# main_unit_shield.net
KiCad netlist of a schematic drawn in EAGLE
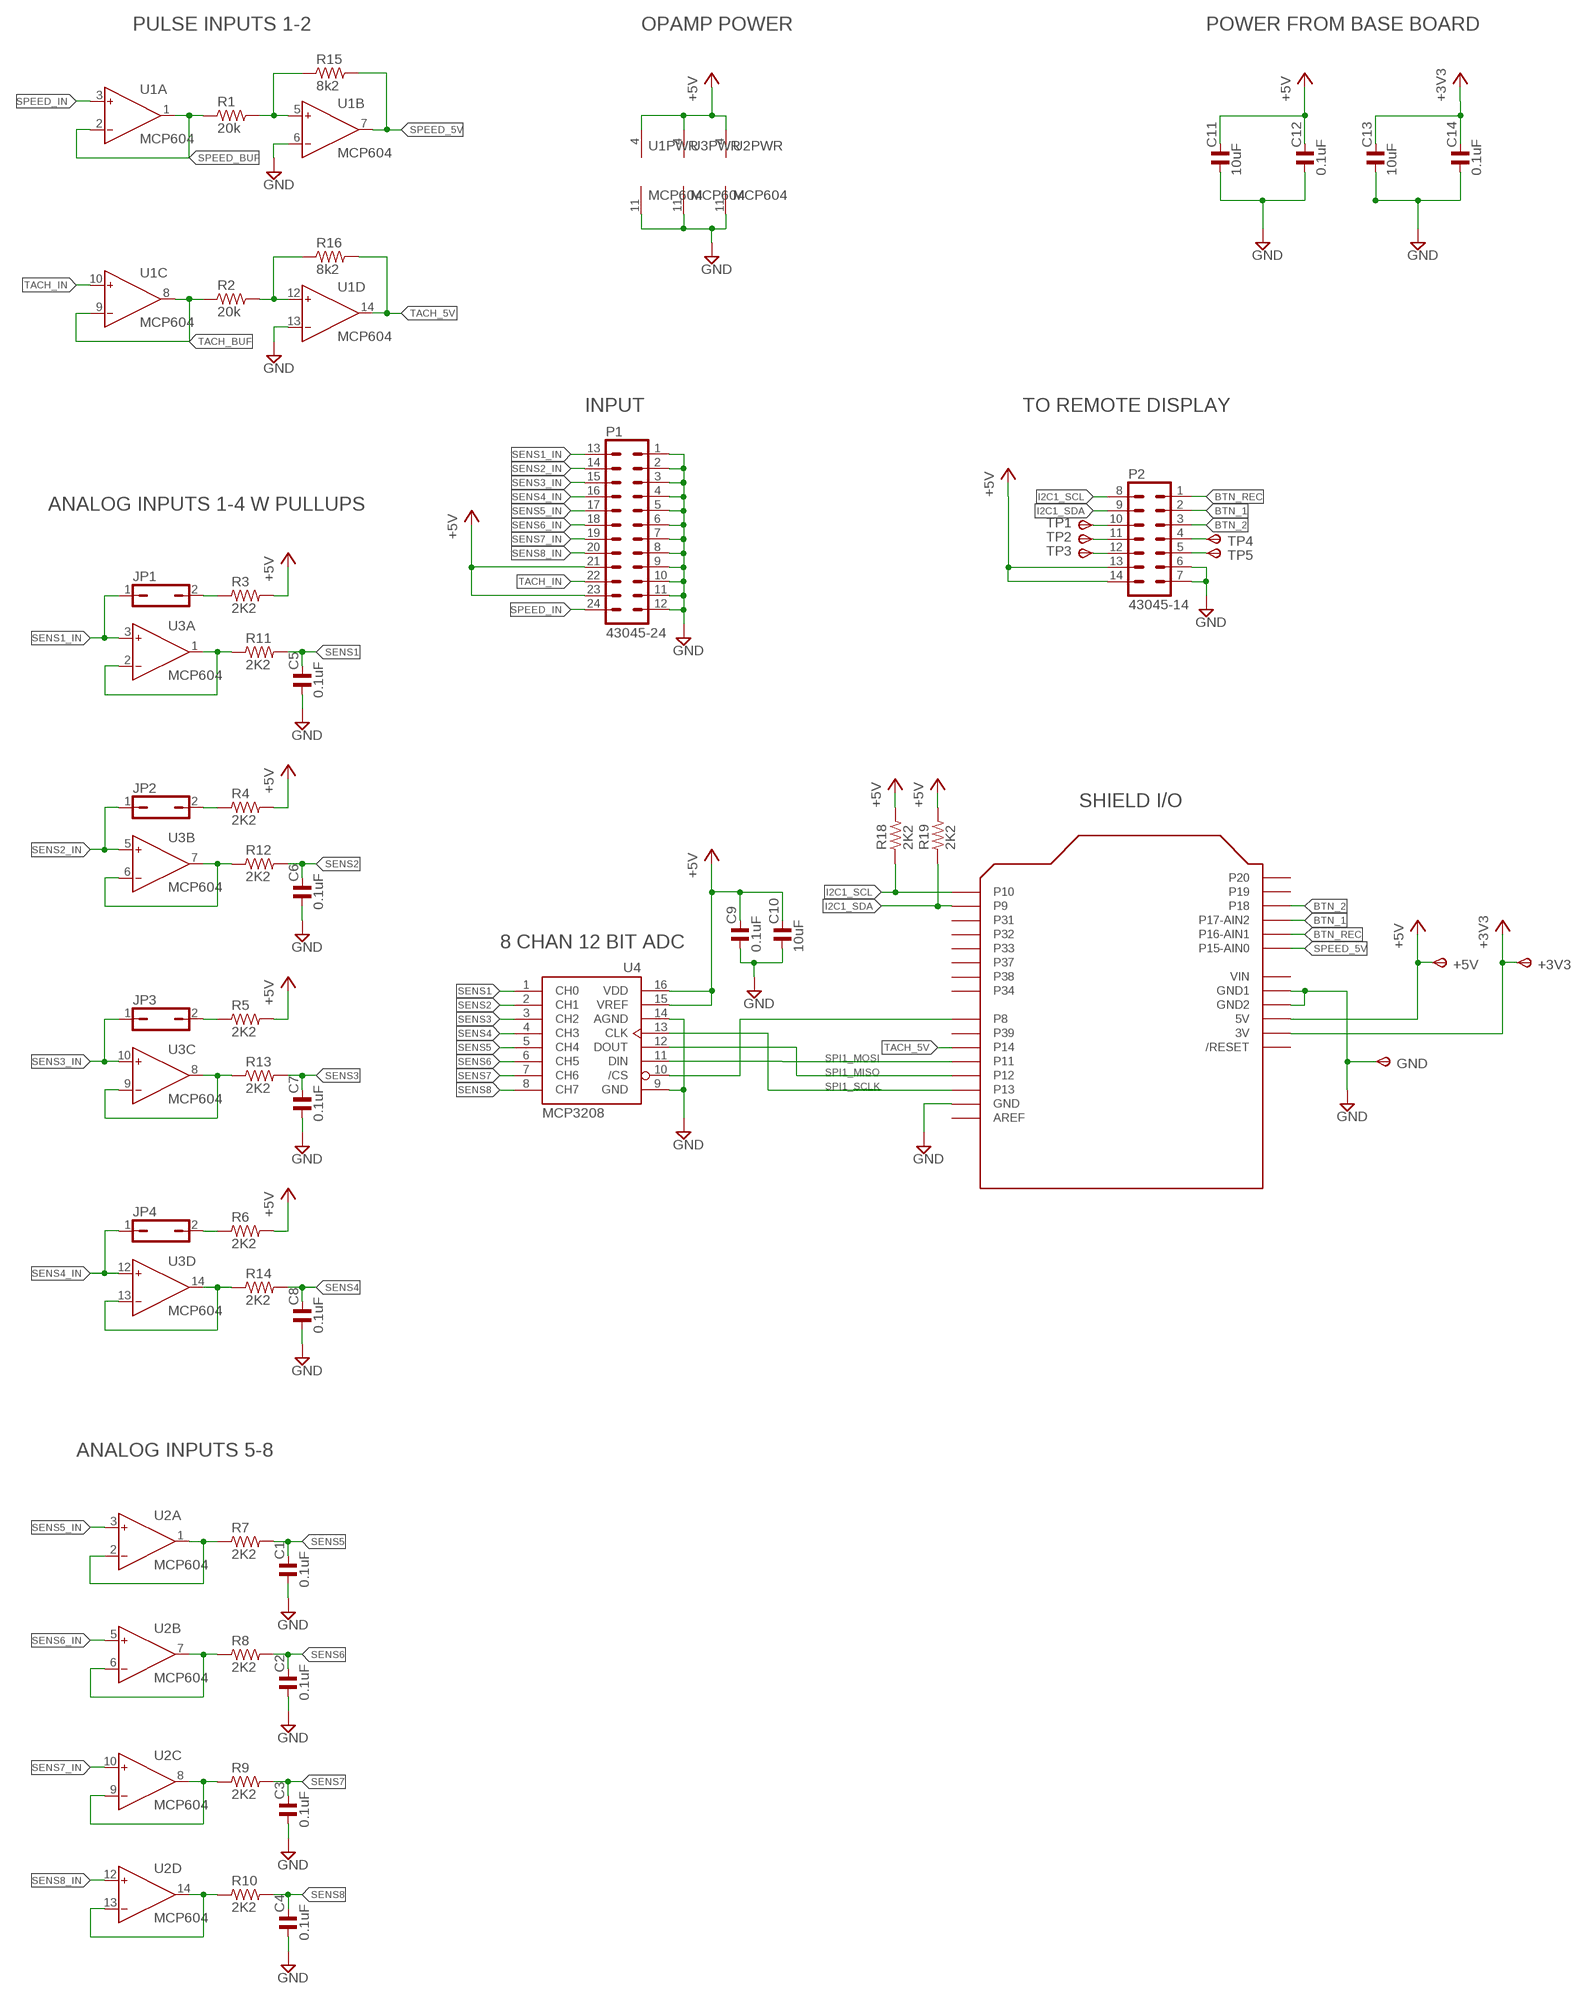
[diagram p0: schematic, sheet 1]

(export (version "E")
  (design (tool "Eeschema 10.0.6"))
  (components
    (comp (ref "+3V3")
      (value "TPSPAD1-13")
      (footprint "eagle-import:P1-13")
      (libsource (lib "eagle-import") (part "TPSPAD1-13"))
    )
    (comp (ref "+5V")
      (value "TPSPAD1-13")
      (footprint "eagle-import:P1-13")
      (libsource (lib "eagle-import") (part "TPSPAD1-13"))
    )
    (comp (ref "C1")
      (value "0.1uF")
      (footprint "eagle-import:C0805")
      (fields (field (name "MPN") "C2012X7R1H104K085AA"))
      (libsource (lib "eagle-import") (part "C_0805"))
    )
    (comp (ref "C2")
      (value "0.1uF")
      (footprint "eagle-import:C0805")
      (fields (field (name "MPN") "C2012X7R1H104K085AA"))
      (libsource (lib "eagle-import") (part "C_0805"))
    )
    (comp (ref "C3")
      (value "0.1uF")
      (footprint "eagle-import:C0805")
      (fields (field (name "MPN") "C2012X7R1H104K085AA"))
      (libsource (lib "eagle-import") (part "C_0805"))
    )
    (comp (ref "C4")
      (value "0.1uF")
      (footprint "eagle-import:C0805")
      (fields (field (name "MPN") "C2012X7R1H104K085AA"))
      (libsource (lib "eagle-import") (part "C_0805"))
    )
    (comp (ref "C5")
      (value "0.1uF")
      (footprint "eagle-import:C0805")
      (fields (field (name "MPN") "C2012X7R1H104K085AA"))
      (libsource (lib "eagle-import") (part "C_0805"))
    )
    (comp (ref "C6")
      (value "0.1uF")
      (footprint "eagle-import:C0805")
      (fields (field (name "MPN") "C2012X7R1H104K085AA"))
      (libsource (lib "eagle-import") (part "C_0805"))
    )
    (comp (ref "C7")
      (value "0.1uF")
      (footprint "eagle-import:C0805")
      (fields (field (name "MPN") "C2012X7R1H104K085AA"))
      (libsource (lib "eagle-import") (part "C_0805"))
    )
    (comp (ref "C8")
      (value "0.1uF")
      (footprint "eagle-import:C0805")
      (fields (field (name "MPN") "C2012X7R1H104K085AA"))
      (libsource (lib "eagle-import") (part "C_0805"))
    )
    (comp (ref "C9")
      (value "0.1uF")
      (footprint "eagle-import:C0805")
      (fields (field (name "MPN") "C2012X7R1H104K085AA"))
      (libsource (lib "eagle-import") (part "C_0805"))
    )
    (comp (ref "C10")
      (value "10uF")
      (footprint "eagle-import:C0805")
      (fields (field (name "MPN") "C2012X5R1E106K125AB"))
      (libsource (lib "eagle-import") (part "C_0805"))
    )
    (comp (ref "C11")
      (value "10uF")
      (footprint "eagle-import:C0805")
      (fields (field (name "MPN") "C2012X5R1E106K125AB"))
      (libsource (lib "eagle-import") (part "C_0805"))
    )
    (comp (ref "C12")
      (value "0.1uF")
      (footprint "eagle-import:C0805")
      (fields (field (name "MPN") "C2012X7R1H104K085AA"))
      (libsource (lib "eagle-import") (part "C_0805"))
    )
    (comp (ref "C13")
      (value "10uF")
      (footprint "eagle-import:C0805")
      (fields (field (name "MPN") "C2012X5R1E106K125AB"))
      (libsource (lib "eagle-import") (part "C_0805"))
    )
    (comp (ref "C14")
      (value "0.1uF")
      (footprint "eagle-import:C0805")
      (fields (field (name "MPN") "C2012X7R1H104K085AA"))
      (libsource (lib "eagle-import") (part "C_0805"))
    )
    (comp (ref "GND")
      (value "TPSPAD1-13")
      (footprint "eagle-import:P1-13")
      (libsource (lib "eagle-import") (part "TPSPAD1-13"))
    )
    (comp (ref "JP1")
      (value "JP1Q")
      (footprint "eagle-import:JP1")
      (fields (field (name "MPN") "969102-0000-DA"))
      (libsource (lib "eagle-import") (part "JP1Q"))
    )
    (comp (ref "JP2")
      (value "JP1Q")
      (footprint "eagle-import:JP1")
      (fields (field (name "MPN") "969102-0000-DA"))
      (libsource (lib "eagle-import") (part "JP1Q"))
    )
    (comp (ref "JP3")
      (value "JP1Q")
      (footprint "eagle-import:JP1")
      (fields (field (name "MPN") "969102-0000-DA"))
      (libsource (lib "eagle-import") (part "JP1Q"))
    )
    (comp (ref "JP4")
      (value "JP1Q")
      (footprint "eagle-import:JP1")
      (fields (field (name "MPN") "969102-0000-DA"))
      (libsource (lib "eagle-import") (part "JP1Q"))
    )
    (comp (ref "P1")
      (value "43045-24")
      (footprint "eagle-import:43045-24")
      (fields (field (name "MF") "MOLEX") (field (name "MPN") "43045-2400"))
      (libsource (lib "eagle-import") (part "43045-24"))
    )
    (comp (ref "P2")
      (value "43045-14")
      (footprint "eagle-import:43045-14")
      (fields (field (name "MPN") "43045-1400"))
      (libsource (lib "eagle-import") (part "43045-14"))
    )
    (comp (ref "R1")
      (value "20k")
      (footprint "eagle-import:R0805")
      (fields (field (name "MF") "VISHAY/DALE") (field (name "MPN") "CRCW080520K0FKEA"))
      (libsource (lib "eagle-import") (part "R_0805"))
    )
    (comp (ref "R2")
      (value "20k")
      (footprint "eagle-import:R0805")
      (fields (field (name "MF") "VISHAY/DALE") (field (name "MPN") "CRCW080520K0FKEA"))
      (libsource (lib "eagle-import") (part "R_0805"))
    )
    (comp (ref "R3")
      (value "2K2")
      (footprint "eagle-import:R0805")
      (fields (field (name "MF") "VISHAY/DALE") (field (name "MPN") "CRCW08052K20FKEA"))
      (libsource (lib "eagle-import") (part "R_0805"))
    )
    (comp (ref "R4")
      (value "2K2")
      (footprint "eagle-import:R0805")
      (fields (field (name "MF") "VISHAY/DALE") (field (name "MPN") "CRCW08052K20FKEA"))
      (libsource (lib "eagle-import") (part "R_0805"))
    )
    (comp (ref "R5")
      (value "2K2")
      (footprint "eagle-import:R0805")
      (fields (field (name "MF") "VISHAY/DALE") (field (name "MPN") "CRCW08052K20FKEA"))
      (libsource (lib "eagle-import") (part "R_0805"))
    )
    (comp (ref "R6")
      (value "2K2")
      (footprint "eagle-import:R0805")
      (fields (field (name "MF") "VISHAY/DALE") (field (name "MPN") "CRCW08052K20FKEA"))
      (libsource (lib "eagle-import") (part "R_0805"))
    )
    (comp (ref "R7")
      (value "2K2")
      (footprint "eagle-import:R0805")
      (fields (field (name "MF") "VISHAY/DALE") (field (name "MPN") "CRCW08052K20FKEA"))
      (libsource (lib "eagle-import") (part "R_0805"))
    )
    (comp (ref "R8")
      (value "2K2")
      (footprint "eagle-import:R0805")
      (fields (field (name "MF") "VISHAY/DALE") (field (name "MPN") "CRCW08052K20FKEA"))
      (libsource (lib "eagle-import") (part "R_0805"))
    )
    (comp (ref "R9")
      (value "2K2")
      (footprint "eagle-import:R0805")
      (fields (field (name "MF") "VISHAY/DALE") (field (name "MPN") "CRCW08052K20FKEA"))
      (libsource (lib "eagle-import") (part "R_0805"))
    )
    (comp (ref "R10")
      (value "2K2")
      (footprint "eagle-import:R0805")
      (fields (field (name "MF") "VISHAY/DALE") (field (name "MPN") "CRCW08052K20FKEA"))
      (libsource (lib "eagle-import") (part "R_0805"))
    )
    (comp (ref "R11")
      (value "2K2")
      (footprint "eagle-import:R0805")
      (fields (field (name "MF") "VISHAY/DALE") (field (name "MPN") "CRCW08052K20FKEA"))
      (libsource (lib "eagle-import") (part "R_0805"))
    )
    (comp (ref "R12")
      (value "2K2")
      (footprint "eagle-import:R0805")
      (fields (field (name "MF") "VISHAY/DALE") (field (name "MPN") "CRCW08052K20FKEA"))
      (libsource (lib "eagle-import") (part "R_0805"))
    )
    (comp (ref "R13")
      (value "2K2")
      (footprint "eagle-import:R0805")
      (fields (field (name "MF") "VISHAY/DALE") (field (name "MPN") "CRCW08052K20FKEA"))
      (libsource (lib "eagle-import") (part "R_0805"))
    )
    (comp (ref "R14")
      (value "2K2")
      (footprint "eagle-import:R0805")
      (fields (field (name "MF") "VISHAY/DALE") (field (name "MPN") "CRCW08052K20FKEA"))
      (libsource (lib "eagle-import") (part "R_0805"))
    )
    (comp (ref "R15")
      (value "8k2")
      (footprint "eagle-import:R0805")
      (fields (field (name "MPN") "CRCW08058K20FKEAHP"))
      (libsource (lib "eagle-import") (part "R_0805"))
    )
    (comp (ref "R16")
      (value "8k2")
      (footprint "eagle-import:R0805")
      (fields (field (name "MPN") "CRCW08058K20FKEAHP"))
      (libsource (lib "eagle-import") (part "R_0805"))
    )
    (comp (ref "R18")
      (value "2K2")
      (footprint "eagle-import:R0805")
      (fields (field (name "MF") "VISHAY/DALE") (field (name "MPN") "CRCW08052K20FKEA"))
      (libsource (lib "eagle-import") (part "R_0805"))
    )
    (comp (ref "R19")
      (value "2K2")
      (footprint "eagle-import:R0805")
      (fields (field (name "MF") "VISHAY/DALE") (field (name "MPN") "CRCW08052K20FKEA"))
      (libsource (lib "eagle-import") (part "R_0805"))
    )
    (comp (ref "TP1")
      (value "TPSPAD1-13")
      (footprint "eagle-import:P1-13")
      (libsource (lib "eagle-import") (part "TPSPAD1-13"))
    )
    (comp (ref "TP2")
      (value "TPSPAD1-13")
      (footprint "eagle-import:P1-13")
      (libsource (lib "eagle-import") (part "TPSPAD1-13"))
    )
    (comp (ref "TP3")
      (value "TPSPAD1-13")
      (footprint "eagle-import:P1-13")
      (libsource (lib "eagle-import") (part "TPSPAD1-13"))
    )
    (comp (ref "TP4")
      (value "TPSPAD1-13")
      (footprint "eagle-import:P1-13")
      (libsource (lib "eagle-import") (part "TPSPAD1-13"))
    )
    (comp (ref "TP5")
      (value "TPSPAD1-13")
      (footprint "eagle-import:P1-13")
      (libsource (lib "eagle-import") (part "TPSPAD1-13"))
    )
    (comp (ref "U1")
      (value "MCP604")
      (footprint "eagle-import:SO14")
      (fields (field (name "MPN") "MCP6044-E/SL") (field (name "OC_NEWARK") "56J7441"))
      (libsource (lib "eagle-import") (part "MCP604"))
    )
    (comp (ref "U2")
      (value "MCP604")
      (footprint "eagle-import:SO14")
      (fields (field (name "MPN") "MCP6044-E/SL") (field (name "OC_NEWARK") "56J7441"))
      (libsource (lib "eagle-import") (part "MCP604"))
    )
    (comp (ref "U3")
      (value "MCP604")
      (footprint "eagle-import:SO14")
      (fields (field (name "MPN") "MCP6044-E/SL") (field (name "OC_NEWARK") "56J7441"))
      (libsource (lib "eagle-import") (part "MCP604"))
    )
    (comp (ref "U4")
      (value "MCP3208")
      (footprint "eagle-import:SO16")
      (fields (field (name "MF") "MICROCHIP") (field (name "MPN") "MCP3208-BI/SL"))
      (libsource (lib "eagle-import") (part "MCP3208"))
    )
    (comp (ref "U5")
      (value "ARDUINOUNO")
      (footprint "eagle-import:ARDUINO")
      (libsource (lib "eagle-import") (part "ARDUINOUNO"))
    )
  )
  (nets
    (net (code "1") (name "+3V3") (class "Default")
      (node (ref "+3V3") (pin "TP") (pinfunction "PP_TP") (pintype "input"))
      (node (ref "C13") (pin "2") (pinfunction "2_2") (pintype "passive"))
      (node (ref "C14") (pin "2") (pinfunction "2_2") (pintype "passive"))
      (node (ref "U5") (pin "3V") (pinfunction "3V_3V") (pintype "power_in"))
    )
    (net (code "2") (name "+5V") (class "Default")
      (node (ref "+5V") (pin "TP") (pinfunction "PP_TP") (pintype "input"))
      (node (ref "C10") (pin "2") (pinfunction "2_2") (pintype "passive"))
      (node (ref "C11") (pin "2") (pinfunction "2_2") (pintype "passive"))
      (node (ref "C12") (pin "2") (pinfunction "2_2") (pintype "passive"))
      (node (ref "C9") (pin "2") (pinfunction "2_2") (pintype "passive"))
      (node (ref "P1") (pin "21") (pinfunction "21_21") (pintype "passive"))
      (node (ref "P1") (pin "23") (pinfunction "23_23") (pintype "passive"))
      (node (ref "P2") (pin "13") (pinfunction "13_13") (pintype "passive"))
      (node (ref "P2") (pin "14") (pinfunction "14_14") (pintype "passive"))
      (node (ref "R18") (pin "2") (pinfunction "2_2") (pintype "passive"))
      (node (ref "R19") (pin "2") (pinfunction "2_2") (pintype "passive"))
      (node (ref "R3") (pin "2") (pinfunction "2_2") (pintype "passive"))
      (node (ref "R4") (pin "2") (pinfunction "2_2") (pintype "passive"))
      (node (ref "R5") (pin "2") (pinfunction "2_2") (pintype "passive"))
      (node (ref "R6") (pin "2") (pinfunction "2_2") (pintype "passive"))
      (node (ref "U1") (pin "4") (pinfunction "V+_4") (pintype "power_in"))
      (node (ref "U2") (pin "4") (pinfunction "V+_4") (pintype "power_in"))
      (node (ref "U3") (pin "4") (pinfunction "V+_4") (pintype "power_in"))
      (node (ref "U4") (pin "15") (pinfunction "VREF_15") (pintype "input"))
      (node (ref "U4") (pin "16") (pinfunction "VDD_16") (pintype "power_in"))
      (node (ref "U5") (pin "5V") (pinfunction "5V_5V") (pintype "power_in"))
    )
    (net (code "3") (name "/SPI1_MISO") (class "Default")
      (node (ref "U4") (pin "12") (pinfunction "DOUT_12") (pintype "output"))
      (node (ref "U5") (pin "D12") (pinfunction "P12_D12") (pintype "bidirectional"))
    )
    (net (code "4") (name "/SPI1_MOSI") (class "Default")
      (node (ref "U4") (pin "11") (pinfunction "DIN_11") (pintype "input"))
      (node (ref "U5") (pin "D11") (pinfunction "P11_D11") (pintype "bidirectional"))
    )
    (net (code "5") (name "/SPI1_SCLK") (class "Default")
      (node (ref "U4") (pin "13") (pinfunction "CLK_13") (pintype "input"))
      (node (ref "U5") (pin "D13") (pinfunction "P13_D13") (pintype "bidirectional"))
    )
    (net (code "6") (name "/VIN") (class "Default")
      (node (ref "U5") (pin "VIN") (pinfunction "VIN_VIN") (pintype "power_in"))
    )
    (net (code "7") (name "BTN_1") (class "Default")
      (node (ref "P2") (pin "2") (pinfunction "2_2") (pintype "passive"))
      (node (ref "U5") (pin "A2") (pinfunction "P17-AIN2_A2") (pintype "bidirectional"))
    )
    (net (code "8") (name "BTN_2") (class "Default")
      (node (ref "P2") (pin "3") (pinfunction "3_3") (pintype "passive"))
      (node (ref "U5") (pin "A3") (pinfunction "P18_A3") (pintype "bidirectional"))
    )
    (net (code "9") (name "BTN_REC") (class "Default")
      (node (ref "P2") (pin "1") (pinfunction "1_1") (pintype "passive"))
      (node (ref "U5") (pin "A1") (pinfunction "P16-AIN1_A1") (pintype "bidirectional"))
    )
    (net (code "10") (name "GND") (class "Default")
      (node (ref "C1") (pin "1") (pinfunction "1_1") (pintype "passive"))
      (node (ref "C10") (pin "1") (pinfunction "1_1") (pintype "passive"))
      (node (ref "C11") (pin "1") (pinfunction "1_1") (pintype "passive"))
      (node (ref "C12") (pin "1") (pinfunction "1_1") (pintype "passive"))
      (node (ref "C13") (pin "1") (pinfunction "1_1") (pintype "passive"))
      (node (ref "C14") (pin "1") (pinfunction "1_1") (pintype "passive"))
      (node (ref "C2") (pin "1") (pinfunction "1_1") (pintype "passive"))
      (node (ref "C3") (pin "1") (pinfunction "1_1") (pintype "passive"))
      (node (ref "C4") (pin "1") (pinfunction "1_1") (pintype "passive"))
      (node (ref "C5") (pin "1") (pinfunction "1_1") (pintype "passive"))
      (node (ref "C6") (pin "1") (pinfunction "1_1") (pintype "passive"))
      (node (ref "C7") (pin "1") (pinfunction "1_1") (pintype "passive"))
      (node (ref "C8") (pin "1") (pinfunction "1_1") (pintype "passive"))
      (node (ref "C9") (pin "1") (pinfunction "1_1") (pintype "passive"))
      (node (ref "GND") (pin "TP") (pinfunction "PP_TP") (pintype "input"))
      (node (ref "P1") (pin "1") (pinfunction "1_1") (pintype "passive"))
      (node (ref "P1") (pin "10") (pinfunction "10_10") (pintype "passive"))
      (node (ref "P1") (pin "11") (pinfunction "11_11") (pintype "passive"))
      (node (ref "P1") (pin "12") (pinfunction "12_12") (pintype "passive"))
      (node (ref "P1") (pin "2") (pinfunction "2_2") (pintype "passive"))
      (node (ref "P1") (pin "3") (pinfunction "3_3") (pintype "passive"))
      (node (ref "P1") (pin "4") (pinfunction "4_4") (pintype "passive"))
      (node (ref "P1") (pin "5") (pinfunction "5_5") (pintype "passive"))
      (node (ref "P1") (pin "6") (pinfunction "6_6") (pintype "passive"))
      (node (ref "P1") (pin "7") (pinfunction "7_7") (pintype "passive"))
      (node (ref "P1") (pin "8") (pinfunction "8_8") (pintype "passive"))
      (node (ref "P1") (pin "9") (pinfunction "9_9") (pintype "passive"))
      (node (ref "P2") (pin "6") (pinfunction "6_6") (pintype "passive"))
      (node (ref "P2") (pin "7") (pinfunction "7_7") (pintype "passive"))
      (node (ref "U1") (pin "11") (pinfunction "V-_11") (pintype "power_in"))
      (node (ref "U1") (pin "13") (pinfunction "IN-_13") (pintype "input"))
      (node (ref "U1") (pin "6") (pinfunction "IN-_6") (pintype "input"))
      (node (ref "U2") (pin "11") (pinfunction "V-_11") (pintype "power_in"))
      (node (ref "U3") (pin "11") (pinfunction "V-_11") (pintype "power_in"))
      (node (ref "U4") (pin "14") (pinfunction "AGND_14") (pintype "power_in"))
      (node (ref "U4") (pin "9") (pinfunction "GND_9") (pintype "power_in"))
      (node (ref "U5") (pin "GND") (pinfunction "GND_GND") (pintype "power_in"))
      (node (ref "U5") (pin "GND1") (pinfunction "GND1_GND1") (pintype "power_in"))
      (node (ref "U5") (pin "GND2") (pinfunction "GND2_GND2") (pintype "power_in"))
    )
    (net (code "11") (name "I2C1_SCL") (class "Default")
      (node (ref "P2") (pin "8") (pinfunction "8_8") (pintype "passive"))
      (node (ref "R18") (pin "1") (pinfunction "1_1") (pintype "passive"))
      (node (ref "U5") (pin "D0") (pinfunction "P10_D0") (pintype "bidirectional"))
    )
    (net (code "12") (name "I2C1_SDA") (class "Default")
      (node (ref "P2") (pin "9") (pinfunction "9_9") (pintype "passive"))
      (node (ref "R19") (pin "1") (pinfunction "1_1") (pintype "passive"))
      (node (ref "U5") (pin "D1") (pinfunction "P9_D1") (pintype "bidirectional"))
    )
    (net (code "13") (name "Net-(JP1-Pad2)") (class "Default")
      (node (ref "JP1") (pin "2") (pinfunction "2_2") (pintype "passive"))
      (node (ref "R3") (pin "1") (pinfunction "1_1") (pintype "passive"))
    )
    (net (code "14") (name "Net-(JP2-Pad2)") (class "Default")
      (node (ref "JP2") (pin "2") (pinfunction "2_2") (pintype "passive"))
      (node (ref "R4") (pin "1") (pinfunction "1_1") (pintype "passive"))
    )
    (net (code "15") (name "Net-(JP3-Pad2)") (class "Default")
      (node (ref "JP3") (pin "2") (pinfunction "2_2") (pintype "passive"))
      (node (ref "R5") (pin "1") (pinfunction "1_1") (pintype "passive"))
    )
    (net (code "16") (name "Net-(JP4-Pad2)") (class "Default")
      (node (ref "JP4") (pin "2") (pinfunction "2_2") (pintype "passive"))
      (node (ref "R6") (pin "1") (pinfunction "1_1") (pintype "passive"))
    )
    (net (code "17") (name "Net-(TP1-PP)") (class "Default")
      (node (ref "P2") (pin "10") (pinfunction "10_10") (pintype "passive"))
      (node (ref "TP1") (pin "TP") (pinfunction "PP_TP") (pintype "input"))
    )
    (net (code "18") (name "Net-(TP2-PP)") (class "Default")
      (node (ref "P2") (pin "11") (pinfunction "11_11") (pintype "passive"))
      (node (ref "TP2") (pin "TP") (pinfunction "PP_TP") (pintype "input"))
    )
    (net (code "19") (name "Net-(TP3-PP)") (class "Default")
      (node (ref "P2") (pin "12") (pinfunction "12_12") (pintype "passive"))
      (node (ref "TP3") (pin "TP") (pinfunction "PP_TP") (pintype "input"))
    )
    (net (code "20") (name "Net-(TP4-PP)") (class "Default")
      (node (ref "P2") (pin "4") (pinfunction "4_4") (pintype "passive"))
      (node (ref "TP4") (pin "TP") (pinfunction "PP_TP") (pintype "input"))
    )
    (net (code "21") (name "Net-(TP5-PP)") (class "Default")
      (node (ref "P2") (pin "5") (pinfunction "5_5") (pintype "passive"))
      (node (ref "TP5") (pin "TP") (pinfunction "PP_TP") (pintype "input"))
    )
    (net (code "22") (name "Net-(U1B-IN+)") (class "Default")
      (node (ref "R1") (pin "2") (pinfunction "2_2") (pintype "passive"))
      (node (ref "R15") (pin "1") (pinfunction "1_1") (pintype "passive"))
      (node (ref "U1") (pin "5") (pinfunction "IN+_5") (pintype "input"))
    )
    (net (code "23") (name "Net-(U1D-IN+)") (class "Default")
      (node (ref "R16") (pin "1") (pinfunction "1_1") (pintype "passive"))
      (node (ref "R2") (pin "2") (pinfunction "2_2") (pintype "passive"))
      (node (ref "U1") (pin "12") (pinfunction "IN+_12") (pintype "input"))
    )
    (net (code "24") (name "Net-(U2A-IN-)") (class "Default")
      (node (ref "R7") (pin "1") (pinfunction "1_1") (pintype "passive"))
      (node (ref "U2") (pin "1") (pinfunction "OUT_1") (pintype "output"))
      (node (ref "U2") (pin "2") (pinfunction "IN-_2") (pintype "input"))
    )
    (net (code "25") (name "Net-(U2B-IN-)") (class "Default")
      (node (ref "R8") (pin "1") (pinfunction "1_1") (pintype "passive"))
      (node (ref "U2") (pin "6") (pinfunction "IN-_6") (pintype "input"))
      (node (ref "U2") (pin "7") (pinfunction "OUT_7") (pintype "output"))
    )
    (net (code "26") (name "Net-(U2C-IN-)") (class "Default")
      (node (ref "R9") (pin "1") (pinfunction "1_1") (pintype "passive"))
      (node (ref "U2") (pin "8") (pinfunction "OUT_8") (pintype "output"))
      (node (ref "U2") (pin "9") (pinfunction "IN-_9") (pintype "input"))
    )
    (net (code "27") (name "Net-(U2D-IN-)") (class "Default")
      (node (ref "R10") (pin "1") (pinfunction "1_1") (pintype "passive"))
      (node (ref "U2") (pin "13") (pinfunction "IN-_13") (pintype "input"))
      (node (ref "U2") (pin "14") (pinfunction "OUT_14") (pintype "output"))
    )
    (net (code "28") (name "Net-(U3A-IN-)") (class "Default")
      (node (ref "R11") (pin "1") (pinfunction "1_1") (pintype "passive"))
      (node (ref "U3") (pin "1") (pinfunction "OUT_1") (pintype "output"))
      (node (ref "U3") (pin "2") (pinfunction "IN-_2") (pintype "input"))
    )
    (net (code "29") (name "Net-(U3B-IN-)") (class "Default")
      (node (ref "R12") (pin "1") (pinfunction "1_1") (pintype "passive"))
      (node (ref "U3") (pin "6") (pinfunction "IN-_6") (pintype "input"))
      (node (ref "U3") (pin "7") (pinfunction "OUT_7") (pintype "output"))
    )
    (net (code "30") (name "Net-(U3C-IN-)") (class "Default")
      (node (ref "R13") (pin "1") (pinfunction "1_1") (pintype "passive"))
      (node (ref "U3") (pin "8") (pinfunction "OUT_8") (pintype "output"))
      (node (ref "U3") (pin "9") (pinfunction "IN-_9") (pintype "input"))
    )
    (net (code "31") (name "Net-(U3D-IN-)") (class "Default")
      (node (ref "R14") (pin "1") (pinfunction "1_1") (pintype "passive"))
      (node (ref "U3") (pin "13") (pinfunction "IN-_13") (pintype "input"))
      (node (ref "U3") (pin "14") (pinfunction "OUT_14") (pintype "output"))
    )
    (net (code "32") (name "Net-(U4-{slash}CS)") (class "Default")
      (node (ref "U4") (pin "10") (pinfunction "/CS_10") (pintype "input"))
      (node (ref "U5") (pin "D8") (pinfunction "P8_D8") (pintype "bidirectional"))
    )
    (net (code "33") (name "SENS1") (class "Default")
      (node (ref "C5") (pin "2") (pinfunction "2_2") (pintype "passive"))
      (node (ref "R11") (pin "2") (pinfunction "2_2") (pintype "passive"))
      (node (ref "U4") (pin "1") (pinfunction "CH0_1") (pintype "input"))
    )
    (net (code "34") (name "SENS1_IN") (class "Default")
      (node (ref "JP1") (pin "1") (pinfunction "1_1") (pintype "passive"))
      (node (ref "P1") (pin "13") (pinfunction "13_13") (pintype "passive"))
      (node (ref "U3") (pin "3") (pinfunction "IN+_3") (pintype "input"))
    )
    (net (code "35") (name "SENS2") (class "Default")
      (node (ref "C6") (pin "2") (pinfunction "2_2") (pintype "passive"))
      (node (ref "R12") (pin "2") (pinfunction "2_2") (pintype "passive"))
      (node (ref "U4") (pin "2") (pinfunction "CH1_2") (pintype "input"))
    )
    (net (code "36") (name "SENS2_IN") (class "Default")
      (node (ref "JP2") (pin "1") (pinfunction "1_1") (pintype "passive"))
      (node (ref "P1") (pin "14") (pinfunction "14_14") (pintype "passive"))
      (node (ref "U3") (pin "5") (pinfunction "IN+_5") (pintype "input"))
    )
    (net (code "37") (name "SENS3") (class "Default")
      (node (ref "C7") (pin "2") (pinfunction "2_2") (pintype "passive"))
      (node (ref "R13") (pin "2") (pinfunction "2_2") (pintype "passive"))
      (node (ref "U4") (pin "3") (pinfunction "CH2_3") (pintype "input"))
    )
    (net (code "38") (name "SENS3_IN") (class "Default")
      (node (ref "JP3") (pin "1") (pinfunction "1_1") (pintype "passive"))
      (node (ref "P1") (pin "15") (pinfunction "15_15") (pintype "passive"))
      (node (ref "U3") (pin "10") (pinfunction "IN+_10") (pintype "input"))
    )
    (net (code "39") (name "SENS4") (class "Default")
      (node (ref "C8") (pin "2") (pinfunction "2_2") (pintype "passive"))
      (node (ref "R14") (pin "2") (pinfunction "2_2") (pintype "passive"))
      (node (ref "U4") (pin "4") (pinfunction "CH3_4") (pintype "input"))
    )
    (net (code "40") (name "SENS4_IN") (class "Default")
      (node (ref "JP4") (pin "1") (pinfunction "1_1") (pintype "passive"))
      (node (ref "P1") (pin "16") (pinfunction "16_16") (pintype "passive"))
      (node (ref "U3") (pin "12") (pinfunction "IN+_12") (pintype "input"))
    )
    (net (code "41") (name "SENS5") (class "Default")
      (node (ref "C1") (pin "2") (pinfunction "2_2") (pintype "passive"))
      (node (ref "R7") (pin "2") (pinfunction "2_2") (pintype "passive"))
      (node (ref "U4") (pin "5") (pinfunction "CH4_5") (pintype "input"))
    )
    (net (code "42") (name "SENS5_IN") (class "Default")
      (node (ref "P1") (pin "17") (pinfunction "17_17") (pintype "passive"))
      (node (ref "U2") (pin "3") (pinfunction "IN+_3") (pintype "input"))
    )
    (net (code "43") (name "SENS6") (class "Default")
      (node (ref "C2") (pin "2") (pinfunction "2_2") (pintype "passive"))
      (node (ref "R8") (pin "2") (pinfunction "2_2") (pintype "passive"))
      (node (ref "U4") (pin "6") (pinfunction "CH5_6") (pintype "input"))
    )
    (net (code "44") (name "SENS6_IN") (class "Default")
      (node (ref "P1") (pin "18") (pinfunction "18_18") (pintype "passive"))
      (node (ref "U2") (pin "5") (pinfunction "IN+_5") (pintype "input"))
    )
    (net (code "45") (name "SENS7") (class "Default")
      (node (ref "C3") (pin "2") (pinfunction "2_2") (pintype "passive"))
      (node (ref "R9") (pin "2") (pinfunction "2_2") (pintype "passive"))
      (node (ref "U4") (pin "7") (pinfunction "CH6_7") (pintype "input"))
    )
    (net (code "46") (name "SENS7_IN") (class "Default")
      (node (ref "P1") (pin "19") (pinfunction "19_19") (pintype "passive"))
      (node (ref "U2") (pin "10") (pinfunction "IN+_10") (pintype "input"))
    )
    (net (code "47") (name "SENS8") (class "Default")
      (node (ref "C4") (pin "2") (pinfunction "2_2") (pintype "passive"))
      (node (ref "R10") (pin "2") (pinfunction "2_2") (pintype "passive"))
      (node (ref "U4") (pin "8") (pinfunction "CH7_8") (pintype "input"))
    )
    (net (code "48") (name "SENS8_IN") (class "Default")
      (node (ref "P1") (pin "20") (pinfunction "20_20") (pintype "passive"))
      (node (ref "U2") (pin "12") (pinfunction "IN+_12") (pintype "input"))
    )
    (net (code "49") (name "SPEED_5V") (class "Default")
      (node (ref "R15") (pin "2") (pinfunction "2_2") (pintype "passive"))
      (node (ref "U1") (pin "7") (pinfunction "OUT_7") (pintype "output"))
      (node (ref "U5") (pin "A0") (pinfunction "P15-AIN0_A0") (pintype "bidirectional"))
    )
    (net (code "50") (name "SPEED_BUF") (class "Default")
      (node (ref "R1") (pin "1") (pinfunction "1_1") (pintype "passive"))
      (node (ref "U1") (pin "1") (pinfunction "OUT_1") (pintype "output"))
      (node (ref "U1") (pin "2") (pinfunction "IN-_2") (pintype "input"))
    )
    (net (code "51") (name "SPEED_IN") (class "Default")
      (node (ref "P1") (pin "24") (pinfunction "24_24") (pintype "passive"))
      (node (ref "U1") (pin "3") (pinfunction "IN+_3") (pintype "input"))
    )
    (net (code "52") (name "TACH_5V") (class "Default")
      (node (ref "R16") (pin "2") (pinfunction "2_2") (pintype "passive"))
      (node (ref "U1") (pin "14") (pinfunction "OUT_14") (pintype "output"))
      (node (ref "U5") (pin "D10") (pinfunction "P14_D10") (pintype "bidirectional"))
    )
    (net (code "53") (name "TACH_BUF") (class "Default")
      (node (ref "R2") (pin "1") (pinfunction "1_1") (pintype "passive"))
      (node (ref "U1") (pin "8") (pinfunction "OUT_8") (pintype "output"))
      (node (ref "U1") (pin "9") (pinfunction "IN-_9") (pintype "input"))
    )
    (net (code "54") (name "TACH_IN") (class "Default")
      (node (ref "P1") (pin "22") (pinfunction "22_22") (pintype "passive"))
      (node (ref "U1") (pin "10") (pinfunction "IN+_10") (pintype "input"))
    )
    (net (code "55") (name "unconnected-(U5-P19-PadA4)") (class "Default")
      (node (ref "U5") (pin "A4") (pinfunction "P19_A4") (pintype "bidirectional"))
    )
    (net (code "56") (name "unconnected-(U5-P20-PadA5)") (class "Default")
      (node (ref "U5") (pin "A5") (pinfunction "P20_A5") (pintype "bidirectional"))
    )
    (net (code "57") (name "unconnected-(U5-P31-PadD2)") (class "Default")
      (node (ref "U5") (pin "D2") (pinfunction "P31_D2") (pintype "bidirectional"))
    )
    (net (code "58") (name "unconnected-(U5-P32-PadD3)") (class "Default")
      (node (ref "U5") (pin "D3") (pinfunction "P32_D3") (pintype "bidirectional"))
    )
    (net (code "59") (name "unconnected-(U5-P33-PadD4)") (class "Default")
      (node (ref "U5") (pin "D4") (pinfunction "P33_D4") (pintype "bidirectional"))
    )
    (net (code "60") (name "unconnected-(U5-P34-PadD7)") (class "Default")
      (node (ref "U5") (pin "D7") (pinfunction "P34_D7") (pintype "bidirectional"))
    )
    (net (code "61") (name "unconnected-(U5-P37-PadD5)") (class "Default")
      (node (ref "U5") (pin "D5") (pinfunction "P37_D5") (pintype "bidirectional"))
    )
    (net (code "62") (name "unconnected-(U5-P38-PadD6)") (class "Default")
      (node (ref "U5") (pin "D6") (pinfunction "P38_D6") (pintype "bidirectional"))
    )
    (net (code "63") (name "unconnected-(U5-P39-PadD9)") (class "Default")
      (node (ref "U5") (pin "D9") (pinfunction "P39_D9") (pintype "bidirectional"))
    )
    (net (code "64") (name "unconnected-(U5-PadAREF)") (class "Default")
      (node (ref "U5") (pin "AREF") (pinfunction "AREF_AREF") (pintype "bidirectional"))
    )
    (net (code "65") (name "unconnected-(U5-{slash}RESET-PadRESET)") (class "Default")
      (node (ref "U5") (pin "RESET") (pinfunction "/RESET_RESET") (pintype "bidirectional"))
    )
  )
)
